# MAX86141_HEG_MINI.net
KiCad netlist of a schematic drawn in EAGLE
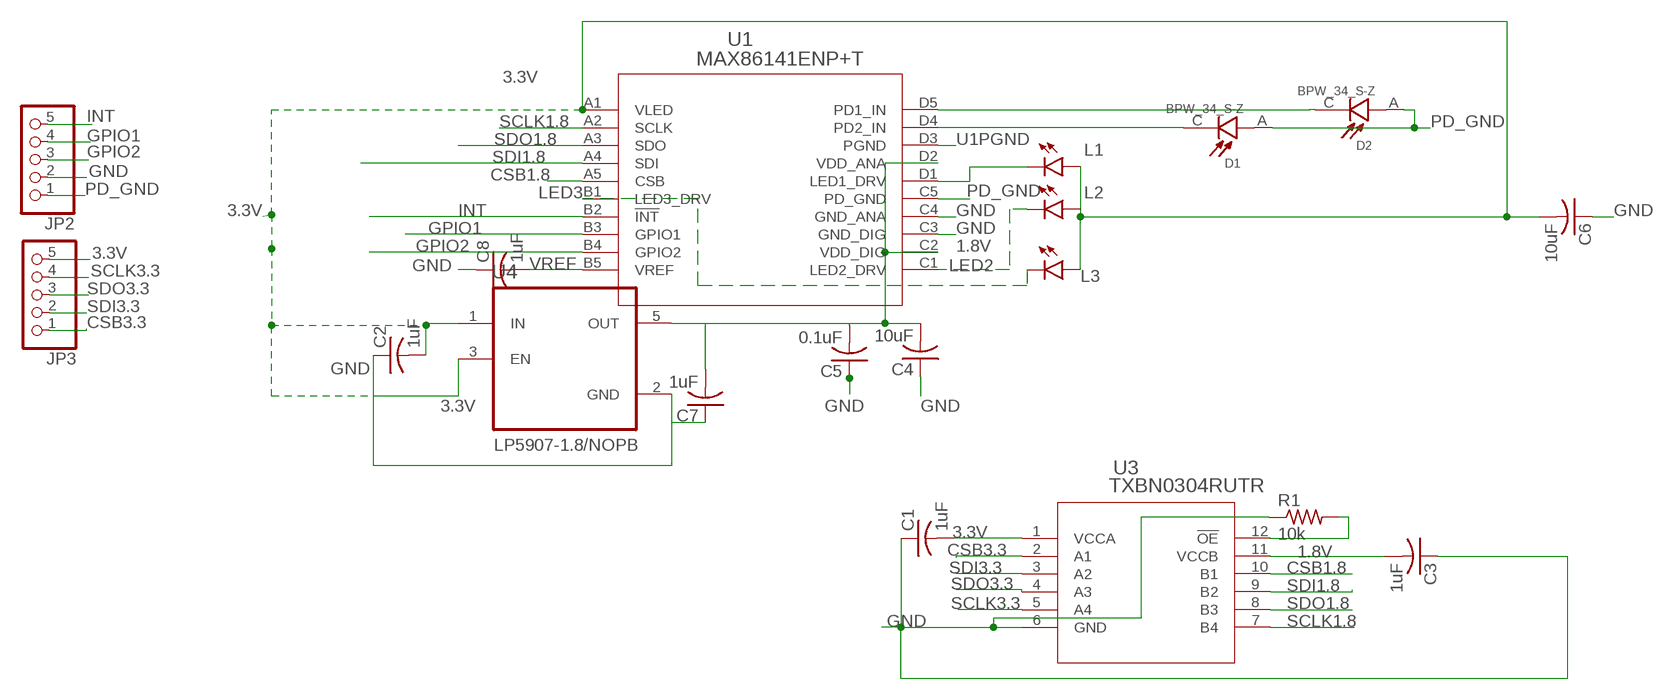
[diagram p0: schematic, sheet 1]

(export (version "E")
  (design (tool "Eeschema 10.0.6"))
  (components
    (comp (ref "C1")
      (value "1uF")
      (footprint "eagle-import:C0402")
      (libsource (lib "eagle-import") (part "C-USC0402"))
    )
    (comp (ref "C2")
      (value "1uF")
      (footprint "eagle-import:C0402")
      (libsource (lib "eagle-import") (part "C-USC0402"))
    )
    (comp (ref "C3")
      (value "1uF")
      (footprint "eagle-import:C0402")
      (libsource (lib "eagle-import") (part "C-USC0402"))
    )
    (comp (ref "C4")
      (value "10uF")
      (footprint "eagle-import:C0402")
      (libsource (lib "eagle-import") (part "C-USC0402"))
    )
    (comp (ref "C5")
      (value "0.1uF")
      (footprint "eagle-import:C0402")
      (libsource (lib "eagle-import") (part "C-USC0402"))
    )
    (comp (ref "C6")
      (value "10uF")
      (footprint "eagle-import:C0402")
      (libsource (lib "eagle-import") (part "C-USC0402"))
    )
    (comp (ref "C7")
      (value "1uF")
      (footprint "eagle-import:C0402")
      (libsource (lib "eagle-import") (part "C-USC0402"))
    )
    (comp (ref "C8")
      (value "1uF")
      (footprint "eagle-import:C0402")
      (libsource (lib "eagle-import") (part "C-USC0402"))
    )
    (comp (ref "D1")
      (value "BPW_34_S-Z")
      (footprint "eagle-import:DIO_BPW_34_S-Z")
      (fields
        (field (name "DIGI-KEY_PART_NUMBER") "475-2659-1-ND")
        (field (name "MF") "OSRAM Opto")
        (field (name "MP") "BPW 34 S-Z")
      )
      (libsource (lib "eagle-import") (part "BPW_34_S-Z"))
    )
    (comp (ref "D2")
      (value "BPW_34_S-Z")
      (footprint "eagle-import:DIO_BPW_34_S-Z")
      (fields
        (field (name "DIGI-KEY_PART_NUMBER") "475-2659-1-ND")
        (field (name "MF") "OSRAM Opto")
        (field (name "MP") "BPW 34 S-Z")
      )
      (libsource (lib "eagle-import") (part "BPW_34_S-Z"))
    )
    (comp (ref "JP2")
      (value "PINHD-1X5")
      (footprint "eagle-import:1X05")
      (libsource (lib "eagle-import") (part "PINHD-1X5"))
    )
    (comp (ref "JP3")
      (value "PINHD-1X5")
      (footprint "eagle-import:1X05")
      (libsource (lib "eagle-import") (part "PINHD-1X5"))
    )
    (comp (ref "L1")
      (value "LEDCHIPLED_1206")
      (footprint "eagle-import:CHIPLED_1206")
      (libsource (lib "eagle-import") (part "LEDCHIPLED_1206"))
    )
    (comp (ref "L2")
      (value "LEDCHIPLED_1206")
      (footprint "eagle-import:CHIPLED_1206")
      (libsource (lib "eagle-import") (part "LEDCHIPLED_1206"))
    )
    (comp (ref "L3")
      (value "LEDCHIPLED_1206")
      (footprint "eagle-import:CHIPLED_1206")
      (libsource (lib "eagle-import") (part "LEDCHIPLED_1206"))
    )
    (comp (ref "R1")
      (value "10k")
      (footprint "eagle-import:R0402")
      (libsource (lib "eagle-import") (part "R-US_R0402"))
    )
    (comp (ref "U1")
      (value "MAX86141ENP+T")
      (footprint "eagle-import:21-100134_N201A2-1_MXM")
      (fields (field (name "COPYRIGHT") "Copyright (C) 2018 Accelerated Designs. All rights reserved"))
      (libsource (lib "eagle-import") (part "MAX86141ENP+T"))
    )
    (comp (ref "U3")
      (value "TXBN0304RUTR")
      (footprint "eagle-import:RUT12")
      (libsource (lib "eagle-import") (part "TXBN0304RUTR"))
    )
    (comp (ref "U4")
      (value "LP5907MFX-3.3/NOPB")
      (footprint "eagle-import:SOT95P280X145-5N")
      (fields (field (name "MF") "Texas Instruments"))
      (libsource (lib "eagle-import") (part "LP5907MFX-3.3/NOPB"))
    )
  )
  (nets
    (net (code "1") (name "/1.8V") (class "Default")
      (node (ref "C3") (pin "2") (pinfunction "2_2") (pintype "passive"))
      (node (ref "C4") (pin "2") (pinfunction "2_2") (pintype "passive"))
      (node (ref "C5") (pin "2") (pinfunction "2_2") (pintype "passive"))
      (node (ref "C7") (pin "2") (pinfunction "2_2") (pintype "passive"))
      (node (ref "U1") (pin "C2") (pinfunction "VDD_DIG_C2") (pintype "power_in"))
      (node (ref "U1") (pin "D2") (pinfunction "VDD_ANA_D2") (pintype "power_in"))
      (node (ref "U3") (pin "11") (pinfunction "VCCB_11") (pintype "power_in"))
      (node (ref "U4") (pin "5") (pinfunction "OUT_5") (pintype "output"))
    )
    (net (code "2") (name "/3.3V") (class "Default")
      (node (ref "C1") (pin "2") (pinfunction "2_2") (pintype "passive"))
      (node (ref "C2") (pin "2") (pinfunction "2_2") (pintype "passive"))
      (node (ref "C6") (pin "2") (pinfunction "2_2") (pintype "passive"))
      (node (ref "JP3") (pin "5") (pinfunction "5_5") (pintype "passive"))
      (node (ref "L1") (pin "A") (pinfunction "A_A") (pintype "passive"))
      (node (ref "L2") (pin "A") (pinfunction "A_A") (pintype "passive"))
      (node (ref "L3") (pin "A") (pinfunction "A_A") (pintype "passive"))
      (node (ref "U1") (pin "A1") (pinfunction "VLED_A1") (pintype "passive"))
      (node (ref "U3") (pin "1") (pinfunction "VCCA_1") (pintype "power_in"))
      (node (ref "U4") (pin "1") (pinfunction "IN_1") (pintype "input"))
      (node (ref "U4") (pin "3") (pinfunction "EN_3") (pintype "input"))
    )
    (net (code "3") (name "/CSB1.8") (class "Default")
      (node (ref "U1") (pin "A5") (pinfunction "CSB_A5") (pintype "passive"))
      (node (ref "U3") (pin "10") (pinfunction "B1_10") (pintype "bidirectional"))
    )
    (net (code "4") (name "/CSB3.3") (class "Default")
      (node (ref "JP3") (pin "1") (pinfunction "1_1") (pintype "passive"))
      (node (ref "U3") (pin "2") (pinfunction "A1_2") (pintype "bidirectional"))
    )
    (net (code "5") (name "/GND") (class "Default")
      (node (ref "C1") (pin "1") (pinfunction "1_1") (pintype "passive"))
      (node (ref "C2") (pin "1") (pinfunction "1_1") (pintype "passive"))
      (node (ref "C3") (pin "1") (pinfunction "1_1") (pintype "passive"))
      (node (ref "C4") (pin "1") (pinfunction "1_1") (pintype "passive"))
      (node (ref "C5") (pin "1") (pinfunction "1_1") (pintype "passive"))
      (node (ref "C6") (pin "1") (pinfunction "1_1") (pintype "passive"))
      (node (ref "C7") (pin "1") (pinfunction "1_1") (pintype "passive"))
      (node (ref "C8") (pin "1") (pinfunction "1_1") (pintype "passive"))
      (node (ref "JP2") (pin "2") (pinfunction "2_2") (pintype "passive"))
      (node (ref "R1") (pin "1") (pinfunction "1_1") (pintype "passive"))
      (node (ref "U1") (pin "C3") (pinfunction "GND_DIG_C3") (pintype "passive"))
      (node (ref "U1") (pin "C4") (pinfunction "GND_ANA_C4") (pintype "passive"))
      (node (ref "U3") (pin "6") (pinfunction "GND_6") (pintype "power_in"))
      (node (ref "U4") (pin "2") (pinfunction "GND_2") (pintype "power_in"))
    )
    (net (code "6") (name "/GPIO1") (class "Default")
      (node (ref "JP2") (pin "4") (pinfunction "4_4") (pintype "passive"))
      (node (ref "U1") (pin "B3") (pinfunction "GPIO1_B3") (pintype "bidirectional"))
    )
    (net (code "7") (name "/GPIO2") (class "Default")
      (node (ref "JP2") (pin "3") (pinfunction "3_3") (pintype "passive"))
      (node (ref "U1") (pin "B4") (pinfunction "GPIO2_B4") (pintype "bidirectional"))
    )
    (net (code "8") (name "/INT") (class "Default")
      (node (ref "JP2") (pin "5") (pinfunction "5_5") (pintype "passive"))
      (node (ref "U1") (pin "B2") (pinfunction "~{INT}_B2") (pintype "passive"))
    )
    (net (code "9") (name "/LED2") (class "Default")
      (node (ref "L2") (pin "C") (pinfunction "C_C") (pintype "passive"))
      (node (ref "U1") (pin "C1") (pinfunction "LED2_DRV_C1") (pintype "bidirectional"))
    )
    (net (code "10") (name "/LED3") (class "Default")
      (node (ref "L3") (pin "C") (pinfunction "C_C") (pintype "passive"))
      (node (ref "U1") (pin "B1") (pinfunction "LED3_DRV_B1") (pintype "bidirectional"))
    )
    (net (code "11") (name "/PD_GND") (class "Default")
      (node (ref "D1") (pin "A") (pinfunction "A_A") (pintype "passive"))
      (node (ref "D2") (pin "A") (pinfunction "A_A") (pintype "passive"))
      (node (ref "JP2") (pin "1") (pinfunction "1_1") (pintype "passive"))
      (node (ref "U1") (pin "C5") (pinfunction "PD_GND_C5") (pintype "passive"))
    )
    (net (code "12") (name "/SCLK1.8") (class "Default")
      (node (ref "U1") (pin "A2") (pinfunction "SCLK_A2") (pintype "passive"))
      (node (ref "U3") (pin "7") (pinfunction "B4_7") (pintype "bidirectional"))
    )
    (net (code "13") (name "/SCLK3.3") (class "Default")
      (node (ref "JP3") (pin "4") (pinfunction "4_4") (pintype "passive"))
      (node (ref "U3") (pin "5") (pinfunction "A4_5") (pintype "bidirectional"))
    )
    (net (code "14") (name "/SDI1.8") (class "Default")
      (node (ref "U1") (pin "A4") (pinfunction "SDI_A4") (pintype "passive"))
      (node (ref "U3") (pin "9") (pinfunction "B2_9") (pintype "bidirectional"))
    )
    (net (code "15") (name "/SDI3.3") (class "Default")
      (node (ref "JP3") (pin "2") (pinfunction "2_2") (pintype "passive"))
      (node (ref "U3") (pin "3") (pinfunction "A2_3") (pintype "bidirectional"))
    )
    (net (code "16") (name "/SDO1.8") (class "Default")
      (node (ref "U1") (pin "A3") (pinfunction "SDO_A3") (pintype "passive"))
      (node (ref "U3") (pin "8") (pinfunction "B3_8") (pintype "bidirectional"))
    )
    (net (code "17") (name "/SDO3.3") (class "Default")
      (node (ref "JP3") (pin "3") (pinfunction "3_3") (pintype "passive"))
      (node (ref "U3") (pin "4") (pinfunction "A3_4") (pintype "bidirectional"))
    )
    (net (code "18") (name "/U1PGND") (class "Default")
      (node (ref "U1") (pin "D3") (pinfunction "PGND_D3") (pintype "passive"))
    )
    (net (code "19") (name "/VREF") (class "Default")
      (node (ref "C8") (pin "2") (pinfunction "2_2") (pintype "passive"))
      (node (ref "U1") (pin "B5") (pinfunction "VREF_B5") (pintype "power_in"))
    )
    (net (code "20") (name "Net-(U1-LED1_DRV)") (class "Default")
      (node (ref "L1") (pin "C") (pinfunction "C_C") (pintype "passive"))
      (node (ref "U1") (pin "D1") (pinfunction "LED1_DRV_D1") (pintype "bidirectional"))
    )
    (net (code "21") (name "Net-(U1-PD1_IN)") (class "Default")
      (node (ref "D2") (pin "C") (pinfunction "C_C") (pintype "passive"))
      (node (ref "U1") (pin "D5") (pinfunction "PD1_IN_D5") (pintype "bidirectional"))
    )
    (net (code "22") (name "Net-(U1-PD2_IN)") (class "Default")
      (node (ref "D1") (pin "C") (pinfunction "C_C") (pintype "passive"))
      (node (ref "U1") (pin "D4") (pinfunction "PD2_IN_D4") (pintype "bidirectional"))
    )
    (net (code "23") (name "Net-(U3-~{OE})") (class "Default")
      (node (ref "R1") (pin "2") (pinfunction "2_2") (pintype "passive"))
      (node (ref "U3") (pin "12") (pinfunction "~{OE}_12") (pintype "input"))
    )
  )
)
